# untitled.net
KiCad netlist of a schematic drawn in EAGLE
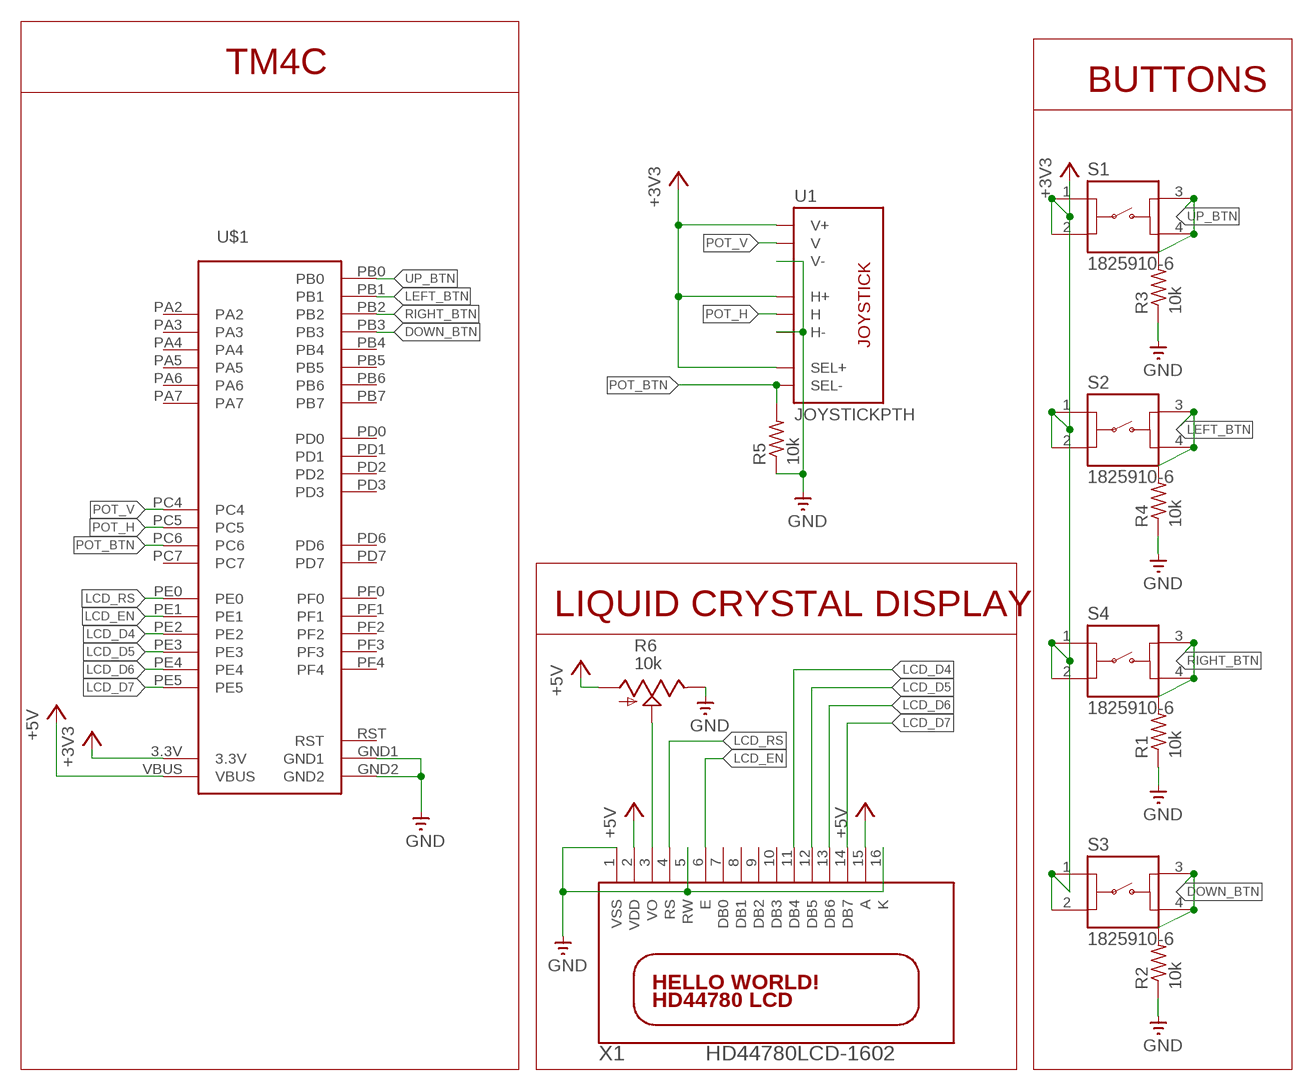
[diagram p0: schematic, sheet 1]

(export (version "E")
  (design (tool "Eeschema 10.0.6"))
  (components
    (comp (ref "R1")
      (value "10k")
      (footprint "eagle-import:R0805")
      (libsource (lib "eagle-import") (part "R-US_R0805"))
    )
    (comp (ref "R2")
      (value "10k")
      (footprint "eagle-import:R0805")
      (libsource (lib "eagle-import") (part "R-US_R0805"))
    )
    (comp (ref "R3")
      (value "10k")
      (footprint "eagle-import:R0805")
      (libsource (lib "eagle-import") (part "R-US_R0805"))
    )
    (comp (ref "R4")
      (value "10k")
      (footprint "eagle-import:R0805")
      (libsource (lib "eagle-import") (part "R-US_R0805"))
    )
    (comp (ref "R5")
      (value "10k")
      (footprint "eagle-import:R0805")
      (libsource (lib "eagle-import") (part "R-US_R0805"))
    )
    (comp (ref "R6")
      (value "10k")
      (footprint "eagle-import:S64W")
      (libsource (lib "eagle-import") (part "TRIM_US-S64W"))
    )
    (comp (ref "S1")
      (value "1825910-6")
      (footprint "eagle-import:1825910-6")
      (fields
        (field (name "DIGIKEY_PART_NUMBER") "450-1650-ND")
        (field (name "MANUFACTURER") "TE Connectivity ALCOSWITCH Switches")
        (field (name "CREATED_BY") " PCBLayout.com")
      )
      (libsource (lib "eagle-import") (part "1825910-6"))
    )
    (comp (ref "S2")
      (value "1825910-6")
      (footprint "eagle-import:1825910-6")
      (fields
        (field (name "DIGIKEY_PART_NUMBER") "450-1650-ND")
        (field (name "MANUFACTURER") "TE Connectivity ALCOSWITCH Switches")
        (field (name "CREATED_BY") " PCBLayout.com")
      )
      (libsource (lib "eagle-import") (part "1825910-6"))
    )
    (comp (ref "S3")
      (value "1825910-6")
      (footprint "eagle-import:1825910-6")
      (fields
        (field (name "DIGIKEY_PART_NUMBER") "450-1650-ND")
        (field (name "MANUFACTURER") "TE Connectivity ALCOSWITCH Switches")
        (field (name "CREATED_BY") " PCBLayout.com")
      )
      (libsource (lib "eagle-import") (part "1825910-6"))
    )
    (comp (ref "S4")
      (value "1825910-6")
      (footprint "eagle-import:1825910-6")
      (fields
        (field (name "DIGIKEY_PART_NUMBER") "450-1650-ND")
        (field (name "MANUFACTURER") "TE Connectivity ALCOSWITCH Switches")
        (field (name "CREATED_BY") " PCBLayout.com")
      )
      (libsource (lib "eagle-import") (part "1825910-6"))
    )
    (comp (ref "U$1")
      (value "STELLARIS-LAUNCHPADSTELLARIS-LAUNCHPAD")
      (footprint "eagle-import:LAUNCHPAD-XL")
      (libsource (lib "eagle-import") (part "STELLARIS-LAUNCHPADSTELLARIS-LAUNCHPAD"))
    )
    (comp (ref "U1")
      (value "JOYSTICKPTH")
      (footprint "eagle-import:JOYSTICK")
      (libsource (lib "eagle-import") (part "JOYSTICKPTH"))
    )
    (comp (ref "X1")
      (value "HD44780LCD-1602")
      (footprint "eagle-import:LCD1602")
      (fields (field (name "SPICEPREFIX") "X"))
      (libsource (lib "eagle-import") (part "HD44780LCD-1602"))
    )
  )
  (nets
    (net (code "1") (name "+3V3") (class "Default")
      (node (ref "S1") (pin "1") (pinfunction "1_1") (pintype "passive"))
      (node (ref "S1") (pin "2") (pinfunction "2_2") (pintype "passive"))
      (node (ref "S2") (pin "1") (pinfunction "1_1") (pintype "passive"))
      (node (ref "S2") (pin "2") (pinfunction "2_2") (pintype "passive"))
      (node (ref "S3") (pin "1") (pinfunction "1_1") (pintype "passive"))
      (node (ref "S3") (pin "2") (pinfunction "2_2") (pintype "passive"))
      (node (ref "S4") (pin "1") (pinfunction "1_1") (pintype "passive"))
      (node (ref "S4") (pin "2") (pinfunction "2_2") (pintype "passive"))
      (node (ref "U$1") (pin "3.3V") (pinfunction "3.3V_3.3V") (pintype "power_in"))
      (node (ref "U1") (pin "B1A") (pinfunction "SEL+_B1A") (pintype "bidirectional"))
      (node (ref "U1") (pin "H1") (pinfunction "H+_H1") (pintype "bidirectional"))
      (node (ref "U1") (pin "V1") (pinfunction "V+_V1") (pintype "bidirectional"))
    )
    (net (code "2") (name "+5V") (class "Default")
      (node (ref "R6") (pin "A") (pinfunction "A_A") (pintype "passive"))
      (node (ref "U$1") (pin "VBUS") (pinfunction "VBUS_VBUS") (pintype "power_in"))
      (node (ref "X1") (pin "15") (pinfunction "A_15") (pintype "input"))
      (node (ref "X1") (pin "2") (pinfunction "VDD_2") (pintype "power_in"))
    )
    (net (code "3") (name "/RST") (class "Default")
      (node (ref "U$1") (pin "RST") (pinfunction "RST_RST") (pintype "power_in"))
    )
    (net (code "4") (name "DOWN_BTN") (class "Default")
      (node (ref "R2") (pin "2") (pinfunction "2_2") (pintype "passive"))
      (node (ref "S3") (pin "3") (pinfunction "3_3") (pintype "passive"))
      (node (ref "S3") (pin "4") (pinfunction "4_4") (pintype "passive"))
      (node (ref "U$1") (pin "PB3") (pinfunction "PB3_PB3") (pintype "bidirectional"))
    )
    (net (code "5") (name "GND") (class "Default")
      (node (ref "R1") (pin "1") (pinfunction "1_1") (pintype "passive"))
      (node (ref "R2") (pin "1") (pinfunction "1_1") (pintype "passive"))
      (node (ref "R3") (pin "1") (pinfunction "1_1") (pintype "passive"))
      (node (ref "R4") (pin "1") (pinfunction "1_1") (pintype "passive"))
      (node (ref "R5") (pin "1") (pinfunction "1_1") (pintype "passive"))
      (node (ref "R6") (pin "E") (pinfunction "E_E") (pintype "passive"))
      (node (ref "U$1") (pin "GND1") (pinfunction "GND1_GND1") (pintype "bidirectional"))
      (node (ref "U$1") (pin "GND2") (pinfunction "GND2_GND2") (pintype "power_in"))
      (node (ref "U1") (pin "H3") (pinfunction "H-_H3") (pintype "bidirectional"))
      (node (ref "U1") (pin "V3") (pinfunction "V-_V3") (pintype "bidirectional"))
      (node (ref "X1") (pin "1") (pinfunction "VSS_1") (pintype "power_in"))
      (node (ref "X1") (pin "16") (pinfunction "K_16") (pintype "input"))
      (node (ref "X1") (pin "5") (pinfunction "RW_5") (pintype "input"))
    )
    (net (code "6") (name "LCD_D4") (class "Default")
      (node (ref "U$1") (pin "PE2") (pinfunction "PE2_PE2") (pintype "bidirectional"))
      (node (ref "X1") (pin "11") (pinfunction "DB4_11") (pintype "bidirectional"))
    )
    (net (code "7") (name "LCD_D5") (class "Default")
      (node (ref "U$1") (pin "PE3") (pinfunction "PE3_PE3") (pintype "bidirectional"))
      (node (ref "X1") (pin "12") (pinfunction "DB5_12") (pintype "bidirectional"))
    )
    (net (code "8") (name "LCD_D6") (class "Default")
      (node (ref "U$1") (pin "PE4") (pinfunction "PE4_PE4") (pintype "bidirectional"))
      (node (ref "X1") (pin "13") (pinfunction "DB6_13") (pintype "bidirectional"))
    )
    (net (code "9") (name "LCD_D7") (class "Default")
      (node (ref "U$1") (pin "PE5") (pinfunction "PE5_PE5") (pintype "bidirectional"))
      (node (ref "X1") (pin "14") (pinfunction "DB7_14") (pintype "bidirectional"))
    )
    (net (code "10") (name "LCD_EN") (class "Default")
      (node (ref "U$1") (pin "PE1") (pinfunction "PE1_PE1") (pintype "bidirectional"))
      (node (ref "X1") (pin "6") (pinfunction "E_6") (pintype "input"))
    )
    (net (code "11") (name "LCD_RS") (class "Default")
      (node (ref "U$1") (pin "PE0") (pinfunction "PE0_PE0") (pintype "bidirectional"))
      (node (ref "X1") (pin "4") (pinfunction "RS_4") (pintype "input"))
    )
    (net (code "12") (name "LEFT_BTN") (class "Default")
      (node (ref "R4") (pin "2") (pinfunction "2_2") (pintype "passive"))
      (node (ref "S2") (pin "3") (pinfunction "3_3") (pintype "passive"))
      (node (ref "S2") (pin "4") (pinfunction "4_4") (pintype "passive"))
      (node (ref "U$1") (pin "PB1") (pinfunction "PB1_PB1") (pintype "bidirectional"))
    )
    (net (code "13") (name "Net-(X1-VO)") (class "Default")
      (node (ref "R6") (pin "S") (pinfunction "S_S") (pintype "passive"))
      (node (ref "X1") (pin "3") (pinfunction "VO_3") (pintype "input"))
    )
    (net (code "14") (name "POT_BTN") (class "Default")
      (node (ref "R5") (pin "2") (pinfunction "2_2") (pintype "passive"))
      (node (ref "U$1") (pin "PC6") (pinfunction "PC6_PC6") (pintype "bidirectional"))
      (node (ref "U1") (pin "B2A") (pinfunction "SEL-_B2A") (pintype "bidirectional"))
    )
    (net (code "15") (name "POT_H") (class "Default")
      (node (ref "U$1") (pin "PC5") (pinfunction "PC5_PC5") (pintype "bidirectional"))
      (node (ref "U1") (pin "H2") (pinfunction "H_H2") (pintype "bidirectional"))
    )
    (net (code "16") (name "POT_V") (class "Default")
      (node (ref "U$1") (pin "PC4") (pinfunction "PC4_PC4") (pintype "bidirectional"))
      (node (ref "U1") (pin "V2") (pinfunction "V_V2") (pintype "bidirectional"))
    )
    (net (code "17") (name "RIGHT_BTN") (class "Default")
      (node (ref "R1") (pin "2") (pinfunction "2_2") (pintype "passive"))
      (node (ref "S4") (pin "3") (pinfunction "3_3") (pintype "passive"))
      (node (ref "S4") (pin "4") (pinfunction "4_4") (pintype "passive"))
      (node (ref "U$1") (pin "PB2") (pinfunction "PB2_PB2") (pintype "bidirectional"))
    )
    (net (code "18") (name "UP_BTN") (class "Default")
      (node (ref "R3") (pin "2") (pinfunction "2_2") (pintype "passive"))
      (node (ref "S1") (pin "3") (pinfunction "3_3") (pintype "passive"))
      (node (ref "S1") (pin "4") (pinfunction "4_4") (pintype "passive"))
      (node (ref "U$1") (pin "PB0") (pinfunction "PB0_PB0") (pintype "bidirectional"))
    )
    (net (code "19") (name "unconnected-(U$1-PadPA2)") (class "Default")
      (node (ref "U$1") (pin "PA2") (pinfunction "PA2_PA2") (pintype "bidirectional"))
    )
    (net (code "20") (name "unconnected-(U$1-PadPA3)") (class "Default")
      (node (ref "U$1") (pin "PA3") (pinfunction "PA3_PA3") (pintype "bidirectional"))
    )
    (net (code "21") (name "unconnected-(U$1-PadPA4)") (class "Default")
      (node (ref "U$1") (pin "PA4") (pinfunction "PA4_PA4") (pintype "bidirectional"))
    )
    (net (code "22") (name "unconnected-(U$1-PadPA5)") (class "Default")
      (node (ref "U$1") (pin "PA5") (pinfunction "PA5_PA5") (pintype "bidirectional"))
    )
    (net (code "23") (name "unconnected-(U$1-PadPA6)") (class "Default")
      (node (ref "U$1") (pin "PA6") (pinfunction "PA6_PA6") (pintype "bidirectional"))
    )
    (net (code "24") (name "unconnected-(U$1-PadPA7)") (class "Default")
      (node (ref "U$1") (pin "PA7") (pinfunction "PA7_PA7") (pintype "bidirectional"))
    )
    (net (code "25") (name "unconnected-(U$1-PadPB4)") (class "Default")
      (node (ref "U$1") (pin "PB4") (pinfunction "PB4_PB4") (pintype "bidirectional"))
    )
    (net (code "26") (name "unconnected-(U$1-PadPB5)") (class "Default")
      (node (ref "U$1") (pin "PB5") (pinfunction "PB5_PB5") (pintype "bidirectional"))
    )
    (net (code "27") (name "unconnected-(U$1-PadPB6)") (class "Default")
      (node (ref "U$1") (pin "PB6") (pinfunction "PB6_PB6") (pintype "bidirectional"))
    )
    (net (code "28") (name "unconnected-(U$1-PadPB7)") (class "Default")
      (node (ref "U$1") (pin "PB7") (pinfunction "PB7_PB7") (pintype "bidirectional"))
    )
    (net (code "29") (name "unconnected-(U$1-PadPC7)") (class "Default")
      (node (ref "U$1") (pin "PC7") (pinfunction "PC7_PC7") (pintype "bidirectional"))
    )
    (net (code "30") (name "unconnected-(U$1-PadPD0)") (class "Default")
      (node (ref "U$1") (pin "PD0") (pinfunction "PD0_PD0") (pintype "bidirectional"))
    )
    (net (code "31") (name "unconnected-(U$1-PadPD1)") (class "Default")
      (node (ref "U$1") (pin "PD1") (pinfunction "PD1_PD1") (pintype "bidirectional"))
    )
    (net (code "32") (name "unconnected-(U$1-PadPD2)") (class "Default")
      (node (ref "U$1") (pin "PD2") (pinfunction "PD2_PD2") (pintype "bidirectional"))
    )
    (net (code "33") (name "unconnected-(U$1-PadPD3)") (class "Default")
      (node (ref "U$1") (pin "PD3") (pinfunction "PD3_PD3") (pintype "bidirectional"))
    )
    (net (code "34") (name "unconnected-(U$1-PadPD6)") (class "Default")
      (node (ref "U$1") (pin "PD6") (pinfunction "PD6_PD6") (pintype "bidirectional"))
    )
    (net (code "35") (name "unconnected-(U$1-PadPD7)") (class "Default")
      (node (ref "U$1") (pin "PD7") (pinfunction "PD7_PD7") (pintype "bidirectional"))
    )
    (net (code "36") (name "unconnected-(U$1-PadPF0)") (class "Default")
      (node (ref "U$1") (pin "PF0") (pinfunction "PF0_PF0") (pintype "bidirectional"))
    )
    (net (code "37") (name "unconnected-(U$1-PadPF1)") (class "Default")
      (node (ref "U$1") (pin "PF1") (pinfunction "PF1_PF1") (pintype "bidirectional"))
    )
    (net (code "38") (name "unconnected-(U$1-PadPF2)") (class "Default")
      (node (ref "U$1") (pin "PF2") (pinfunction "PF2_PF2") (pintype "bidirectional"))
    )
    (net (code "39") (name "unconnected-(U$1-PadPF3)") (class "Default")
      (node (ref "U$1") (pin "PF3") (pinfunction "PF3_PF3") (pintype "bidirectional"))
    )
    (net (code "40") (name "unconnected-(U$1-PadPF4)") (class "Default")
      (node (ref "U$1") (pin "PF4") (pinfunction "PF4_PF4") (pintype "bidirectional"))
    )
    (net (code "41") (name "unconnected-(X1-DB0-Pad7)") (class "Default")
      (node (ref "X1") (pin "7") (pinfunction "DB0_7") (pintype "bidirectional"))
    )
    (net (code "42") (name "unconnected-(X1-DB1-Pad8)") (class "Default")
      (node (ref "X1") (pin "8") (pinfunction "DB1_8") (pintype "bidirectional"))
    )
    (net (code "43") (name "unconnected-(X1-DB2-Pad9)") (class "Default")
      (node (ref "X1") (pin "9") (pinfunction "DB2_9") (pintype "bidirectional"))
    )
    (net (code "44") (name "unconnected-(X1-DB3-Pad10)") (class "Default")
      (node (ref "X1") (pin "10") (pinfunction "DB3_10") (pintype "bidirectional"))
    )
  )
)
